# blinkenlights.net
KiCad netlist of a schematic drawn in Altium Designer
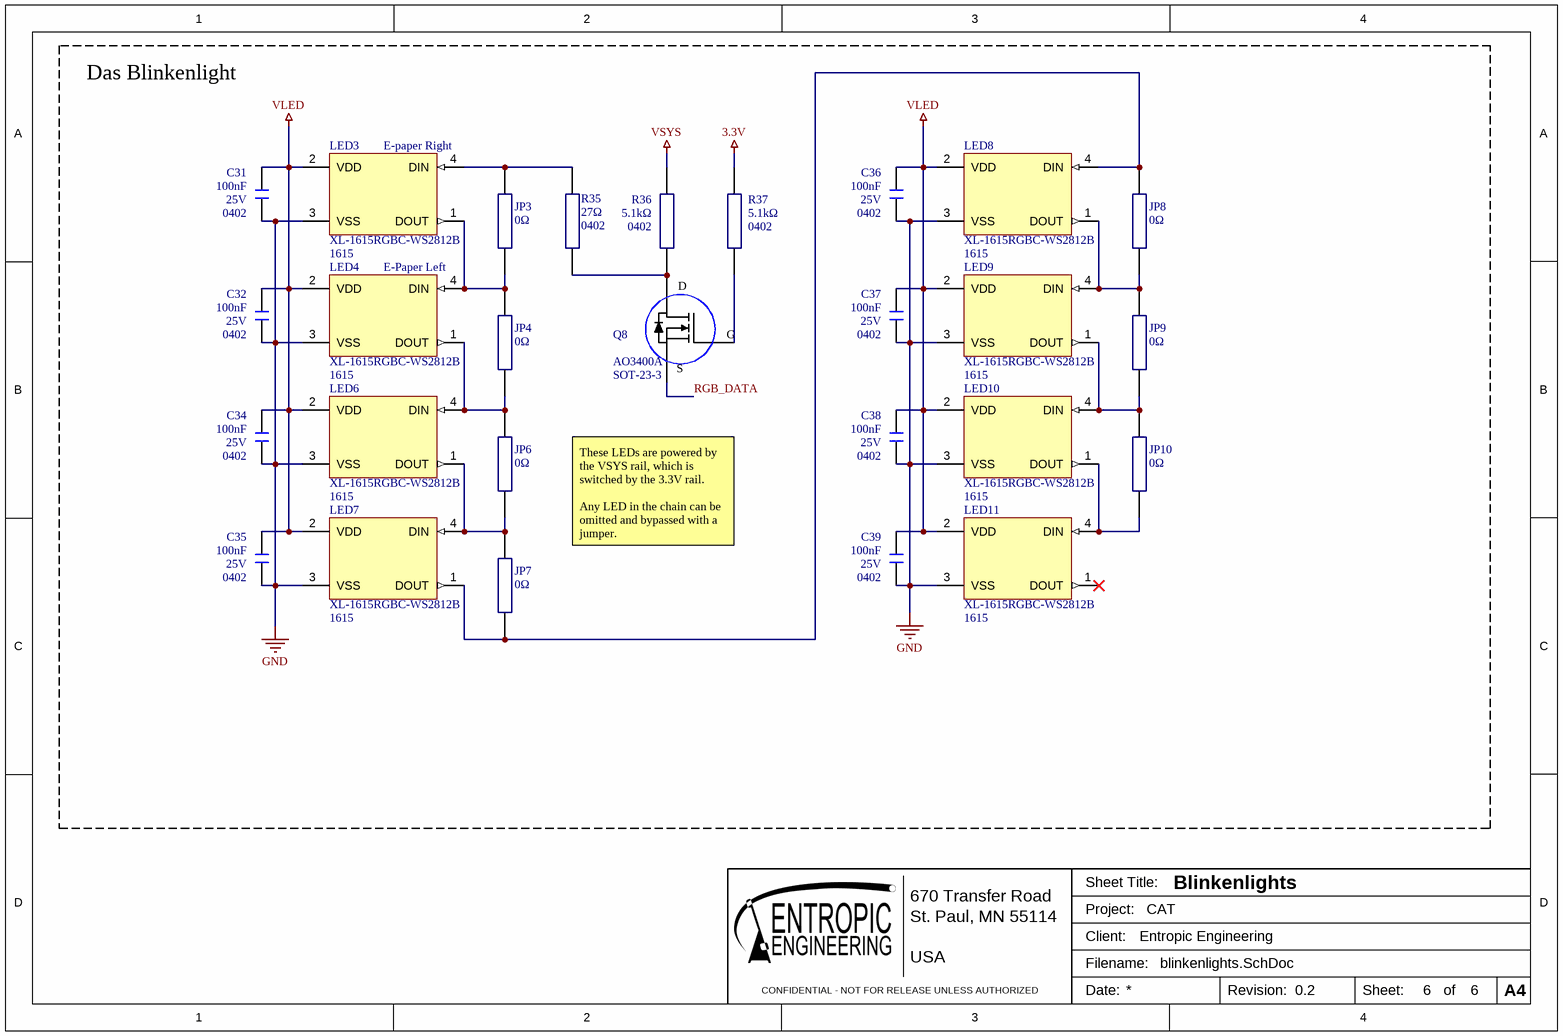
[diagram p0: blinkenlights.SchDoc]

(export (version "E")
  (design (tool "Eeschema 10.0.6"))
  (components
    (comp (ref "C31")
      (value "GRM155R71E104KE14D")
      (footprint "0402_capacitor")
      (description "100 nF, 25 V, X7R, 0402 Chip capacitor")
      (fields
        (field (name "MANUFACTURER") "Murata")
        (field (name "TOLERANCE") "10%")
        (field (name "CASE CODE (IMPERIAL)") "0402")
        (field (name "VOLTAGE") "25V")
        (field (name "CAPACITANCE") "100nF")
      )
      (libsource (lib "cat") (part "GRM155R71E104KE14D"))
    )
    (comp (ref "C32")
      (value "GRM155R71E104KE14D")
      (footprint "0402_capacitor")
      (description "100 nF, 25 V, X7R, 0402 Chip capacitor")
      (fields
        (field (name "MANUFACTURER") "Murata")
        (field (name "TOLERANCE") "10%")
        (field (name "CASE CODE (IMPERIAL)") "0402")
        (field (name "VOLTAGE") "25V")
        (field (name "CAPACITANCE") "100nF")
      )
      (libsource (lib "cat") (part "GRM155R71E104KE14D"))
    )
    (comp (ref "C34")
      (value "GRM155R71E104KE14D")
      (footprint "0402_capacitor")
      (description "100 nF, 25 V, X7R, 0402 Chip capacitor")
      (fields
        (field (name "MANUFACTURER") "Murata")
        (field (name "TOLERANCE") "10%")
        (field (name "CASE CODE (IMPERIAL)") "0402")
        (field (name "VOLTAGE") "25V")
        (field (name "CAPACITANCE") "100nF")
      )
      (libsource (lib "cat") (part "GRM155R71E104KE14D"))
    )
    (comp (ref "C35")
      (value "GRM155R71E104KE14D")
      (footprint "0402_capacitor")
      (description "100 nF, 25 V, X7R, 0402 Chip capacitor")
      (fields
        (field (name "MANUFACTURER") "Murata")
        (field (name "TOLERANCE") "10%")
        (field (name "CASE CODE (IMPERIAL)") "0402")
        (field (name "VOLTAGE") "25V")
        (field (name "CAPACITANCE") "100nF")
      )
      (libsource (lib "cat") (part "GRM155R71E104KE14D"))
    )
    (comp (ref "C36")
      (value "GRM155R71E104KE14D")
      (footprint "0402_capacitor")
      (description "100 nF, 25 V, X7R, 0402 Chip capacitor")
      (fields
        (field (name "MANUFACTURER") "Murata")
        (field (name "TOLERANCE") "10%")
        (field (name "CASE CODE (IMPERIAL)") "0402")
        (field (name "VOLTAGE") "25V")
        (field (name "CAPACITANCE") "100nF")
      )
      (libsource (lib "cat") (part "GRM155R71E104KE14D"))
    )
    (comp (ref "C37")
      (value "GRM155R71E104KE14D")
      (footprint "0402_capacitor")
      (description "100 nF, 25 V, X7R, 0402 Chip capacitor")
      (fields
        (field (name "MANUFACTURER") "Murata")
        (field (name "TOLERANCE") "10%")
        (field (name "CASE CODE (IMPERIAL)") "0402")
        (field (name "VOLTAGE") "25V")
        (field (name "CAPACITANCE") "100nF")
      )
      (libsource (lib "cat") (part "GRM155R71E104KE14D"))
    )
    (comp (ref "C38")
      (value "GRM155R71E104KE14D")
      (footprint "0402_capacitor")
      (description "100 nF, 25 V, X7R, 0402 Chip capacitor")
      (fields
        (field (name "MANUFACTURER") "Murata")
        (field (name "TOLERANCE") "10%")
        (field (name "CASE CODE (IMPERIAL)") "0402")
        (field (name "VOLTAGE") "25V")
        (field (name "CAPACITANCE") "100nF")
      )
      (libsource (lib "cat") (part "GRM155R71E104KE14D"))
    )
    (comp (ref "C39")
      (value "GRM155R71E104KE14D")
      (footprint "0402_capacitor")
      (description "100 nF, 25 V, X7R, 0402 Chip capacitor")
      (fields
        (field (name "MANUFACTURER") "Murata")
        (field (name "TOLERANCE") "10%")
        (field (name "CASE CODE (IMPERIAL)") "0402")
        (field (name "VOLTAGE") "25V")
        (field (name "CAPACITANCE") "100nF")
      )
      (libsource (lib "cat") (part "GRM155R71E104KE14D"))
    )
    (comp (ref "JP3")
      (value "0Ω")
      (footprint "0402_resistor")
      (description "0 Ω, 0402 Chip resistor (jumper)")
      (fields
        (field (name "MANUFACTURER") "Yageo")
        (field (name "MANUFACTURER PART NUMBER") "RC0402FR-070RL")
      )
      (libsource (lib "cat") (part "RC0402FR-070RL"))
    )
    (comp (ref "JP4")
      (value "0Ω")
      (footprint "0402_resistor")
      (description "0 Ω, 0402 Chip resistor (jumper)")
      (fields
        (field (name "MANUFACTURER") "Yageo")
        (field (name "MANUFACTURER PART NUMBER") "RC0402FR-070RL")
      )
      (libsource (lib "cat") (part "RC0402FR-070RL"))
    )
    (comp (ref "JP6")
      (value "0Ω")
      (footprint "0402_resistor")
      (description "0 Ω, 0402 Chip resistor (jumper)")
      (fields
        (field (name "MANUFACTURER") "Yageo")
        (field (name "MANUFACTURER PART NUMBER") "RC0402FR-070RL")
      )
      (libsource (lib "cat") (part "RC0402FR-070RL"))
    )
    (comp (ref "JP7")
      (value "0Ω")
      (footprint "0402_resistor")
      (description "0 Ω, 0402 Chip resistor (jumper)")
      (fields
        (field (name "MANUFACTURER") "Yageo")
        (field (name "MANUFACTURER PART NUMBER") "RC0402FR-070RL")
      )
      (libsource (lib "cat") (part "RC0402FR-070RL"))
    )
    (comp (ref "JP8")
      (value "0Ω")
      (footprint "0402_resistor")
      (description "0 Ω, 0402 Chip resistor (jumper)")
      (fields
        (field (name "MANUFACTURER") "Yageo")
        (field (name "MANUFACTURER PART NUMBER") "RC0402FR-070RL")
      )
      (libsource (lib "cat") (part "RC0402FR-070RL"))
    )
    (comp (ref "JP9")
      (value "0Ω")
      (footprint "0402_resistor")
      (description "0 Ω, 0402 Chip resistor (jumper)")
      (fields
        (field (name "MANUFACTURER") "Yageo")
        (field (name "MANUFACTURER PART NUMBER") "RC0402FR-070RL")
      )
      (libsource (lib "cat") (part "RC0402FR-070RL"))
    )
    (comp (ref "JP10")
      (value "0Ω")
      (footprint "0402_resistor")
      (description "0 Ω, 0402 Chip resistor (jumper)")
      (fields
        (field (name "MANUFACTURER") "Yageo")
        (field (name "MANUFACTURER PART NUMBER") "RC0402FR-070RL")
      )
      (libsource (lib "cat") (part "RC0402FR-070RL"))
    )
    (comp (ref "LED3")
      (value "E-paper Right")
      (footprint "XL-1615RGBC-WS2812B")
      (description "1-wire addressable RGB LED, 1615")
      (fields
        (field (name "MANUFACTURER") "XINGLIGHT")
        (field (name "MANUFACTURER PART NUMBER") "XL-1615RGBC-WS2812B")
        (field (name "PACKAGE") "1615")
      )
      (libsource (lib "cat") (part "XL-1615RGBC-WS2812B"))
    )
    (comp (ref "LED4")
      (value "E-Paper Left")
      (footprint "XL-1615RGBC-WS2812B")
      (description "1-wire addressable RGB LED, 1615")
      (fields
        (field (name "MANUFACTURER") "XINGLIGHT")
        (field (name "MANUFACTURER PART NUMBER") "XL-1615RGBC-WS2812B")
        (field (name "PACKAGE") "1615")
      )
      (libsource (lib "cat") (part "XL-1615RGBC-WS2812B"))
    )
    (comp (ref "LED6")
      (value "XL-1615RGBC-WS2812B")
      (footprint "XL-1615RGBC-WS2812B")
      (description "1-wire addressable RGB LED, 1615")
      (fields
        (field (name "MANUFACTURER") "XINGLIGHT")
        (field (name "MANUFACTURER PART NUMBER") "XL-1615RGBC-WS2812B")
        (field (name "PACKAGE") "1615")
      )
      (libsource (lib "cat") (part "XL-1615RGBC-WS2812B"))
    )
    (comp (ref "LED7")
      (value "WS2812B")
      (footprint "XL-1615RGBC-WS2812B")
      (description "1-wire addressable RGB LED, 1615")
      (fields
        (field (name "MANUFACTURER") "XINGLIGHT")
        (field (name "MANUFACTURER PART NUMBER") "XL-1615RGBC-WS2812B")
        (field (name "PACKAGE") "1615")
      )
      (libsource (lib "cat") (part "XL-1615RGBC-WS2812B"))
    )
    (comp (ref "LED8")
      (value "XL-1615RGBC-WS2812B")
      (footprint "XL-1615RGBC-WS2812B")
      (description "1-wire addressable RGB LED, 1615")
      (fields
        (field (name "MANUFACTURER") "XINGLIGHT")
        (field (name "MANUFACTURER PART NUMBER") "XL-1615RGBC-WS2812B")
        (field (name "PACKAGE") "1615")
      )
      (libsource (lib "cat") (part "XL-1615RGBC-WS2812B"))
    )
    (comp (ref "LED9")
      (value "WS2812B")
      (footprint "XL-1615RGBC-WS2812B")
      (description "1-wire addressable RGB LED, 1615")
      (fields
        (field (name "MANUFACTURER") "XINGLIGHT")
        (field (name "MANUFACTURER PART NUMBER") "XL-1615RGBC-WS2812B")
        (field (name "PACKAGE") "1615")
      )
      (libsource (lib "cat") (part "XL-1615RGBC-WS2812B"))
    )
    (comp (ref "LED10")
      (value "XL-1615RGBC-WS2812B")
      (footprint "XL-1615RGBC-WS2812B")
      (description "1-wire addressable RGB LED, 1615")
      (fields
        (field (name "MANUFACTURER") "XINGLIGHT")
        (field (name "MANUFACTURER PART NUMBER") "XL-1615RGBC-WS2812B")
        (field (name "PACKAGE") "1615")
      )
      (libsource (lib "cat") (part "XL-1615RGBC-WS2812B"))
    )
    (comp (ref "LED11")
      (value "WS2812B")
      (footprint "XL-1615RGBC-WS2812B")
      (description "1-wire addressable RGB LED, 1615")
      (fields
        (field (name "MANUFACTURER") "XINGLIGHT")
        (field (name "MANUFACTURER PART NUMBER") "XL-1615RGBC-WS2812B")
        (field (name "PACKAGE") "1615")
      )
      (libsource (lib "cat") (part "XL-1615RGBC-WS2812B"))
    )
    (comp (ref "Q8")
      (value "N-FET")
      (footprint "SOT95P280X115-3N")
      (description "N-FET, 30V, 5.7A, SOT-23-3")
      (fields
        (field (name "MANUFACTURER") "Alpha & Omega Semiconductor")
        (field (name "CASE/PACKAGE") "SOT-23-3")
        (field (name "MANUFACTURER PART NUMBER") "AO3400A")
        (field (name "HOUSE_PART_NUMBER") "AO3400A")
      )
      (libsource (lib "cat") (part "AO3400A"))
    )
    (comp (ref "R35")
      (value "RMCF0402FT27R0")
      (footprint "0402_resistor")
      (description "27 Ω, 0402 Chip resistor")
      (fields
        (field (name "MANUFACTURER") "Stackpole Electronics")
        (field (name "TOLERANCE") "1%")
        (field (name "RESISTANCE") "27Ω")
        (field (name "SIZE CODE") "0402")
      )
      (libsource (lib "cat") (part "RMCF0402FT27R0"))
    )
    (comp (ref "R36")
      (value "5.1kΩ")
      (footprint "0402_resistor")
      (description "5.1 kΩ, 0402 Chip resistor")
      (fields
        (field (name "MANUFACTURER") "Yageo")
        (field (name "MANUFACTURER PART NUMBER") "RC0402FR-075K1L")
        (field (name "CASE/PACKAGE") "0402")
      )
      (libsource (lib "cat") (part "RC0402FR-075K1L"))
    )
    (comp (ref "R37")
      (value "5.1kΩ")
      (footprint "0402_resistor")
      (description "5.1 kΩ, 0402 Chip resistor")
      (fields
        (field (name "MANUFACTURER") "Yageo")
        (field (name "MANUFACTURER PART NUMBER") "RC0402FR-075K1L")
        (field (name "CASE/PACKAGE") "0402")
      )
      (libsource (lib "cat") (part "RC0402FR-075K1L"))
    )
  )
  (nets
    (net (code "1") (name "/RGB_DATA") (class "Default")
      (node (ref "Q8") (pin "2") (pinfunction "S_2") (pintype "passive"))
    )
    (net (code "2") (name "3.3V") (class "Default")
      (node (ref "R37") (pin "2") (pinfunction "2_2") (pintype "passive"))
    )
    (net (code "3") (name "GND") (class "Default")
      (node (ref "C31") (pin "1") (pinfunction "1_1") (pintype "passive"))
      (node (ref "C32") (pin "1") (pinfunction "1_1") (pintype "passive"))
      (node (ref "C34") (pin "1") (pinfunction "1_1") (pintype "passive"))
      (node (ref "C35") (pin "1") (pinfunction "1_1") (pintype "passive"))
      (node (ref "C36") (pin "1") (pinfunction "1_1") (pintype "passive"))
      (node (ref "C37") (pin "1") (pinfunction "1_1") (pintype "passive"))
      (node (ref "C38") (pin "1") (pinfunction "1_1") (pintype "passive"))
      (node (ref "C39") (pin "1") (pinfunction "1_1") (pintype "passive"))
      (node (ref "LED10") (pin "3") (pinfunction "VSS_3") (pintype "power_in"))
      (node (ref "LED11") (pin "3") (pinfunction "VSS_3") (pintype "power_in"))
      (node (ref "LED3") (pin "3") (pinfunction "VSS_3") (pintype "power_in"))
      (node (ref "LED4") (pin "3") (pinfunction "VSS_3") (pintype "power_in"))
      (node (ref "LED6") (pin "3") (pinfunction "VSS_3") (pintype "power_in"))
      (node (ref "LED7") (pin "3") (pinfunction "VSS_3") (pintype "power_in"))
      (node (ref "LED8") (pin "3") (pinfunction "VSS_3") (pintype "power_in"))
      (node (ref "LED9") (pin "3") (pinfunction "VSS_3") (pintype "power_in"))
    )
    (net (code "4") (name "Net-(LED3-DIN)") (class "Default")
      (node (ref "JP3") (pin "1") (pinfunction "1_1") (pintype "passive"))
      (node (ref "LED3") (pin "4") (pinfunction "DIN_4") (pintype "input"))
      (node (ref "R35") (pin "2") (pinfunction "2_2") (pintype "passive"))
    )
    (net (code "5") (name "Net-(LED3-DOUT)") (class "Default")
      (node (ref "JP3") (pin "2") (pinfunction "2_2") (pintype "passive"))
      (node (ref "JP4") (pin "1") (pinfunction "1_1") (pintype "passive"))
      (node (ref "LED3") (pin "1") (pinfunction "DOUT_1") (pintype "output"))
      (node (ref "LED4") (pin "4") (pinfunction "DIN_4") (pintype "input"))
    )
    (net (code "6") (name "Net-(LED4-DOUT)") (class "Default")
      (node (ref "JP4") (pin "2") (pinfunction "2_2") (pintype "passive"))
      (node (ref "JP6") (pin "1") (pinfunction "1_1") (pintype "passive"))
      (node (ref "LED4") (pin "1") (pinfunction "DOUT_1") (pintype "output"))
      (node (ref "LED6") (pin "4") (pinfunction "DIN_4") (pintype "input"))
    )
    (net (code "7") (name "Net-(LED6-DOUT)") (class "Default")
      (node (ref "JP6") (pin "2") (pinfunction "2_2") (pintype "passive"))
      (node (ref "JP7") (pin "1") (pinfunction "1_1") (pintype "passive"))
      (node (ref "LED6") (pin "1") (pinfunction "DOUT_1") (pintype "output"))
      (node (ref "LED7") (pin "4") (pinfunction "DIN_4") (pintype "input"))
    )
    (net (code "8") (name "Net-(LED7-DOUT)") (class "Default")
      (node (ref "JP7") (pin "2") (pinfunction "2_2") (pintype "passive"))
      (node (ref "JP8") (pin "1") (pinfunction "1_1") (pintype "passive"))
      (node (ref "LED7") (pin "1") (pinfunction "DOUT_1") (pintype "output"))
      (node (ref "LED8") (pin "4") (pinfunction "DIN_4") (pintype "input"))
    )
    (net (code "9") (name "Net-(LED8-DOUT)") (class "Default")
      (node (ref "JP8") (pin "2") (pinfunction "2_2") (pintype "passive"))
      (node (ref "JP9") (pin "1") (pinfunction "1_1") (pintype "passive"))
      (node (ref "LED8") (pin "1") (pinfunction "DOUT_1") (pintype "output"))
      (node (ref "LED9") (pin "4") (pinfunction "DIN_4") (pintype "input"))
    )
    (net (code "10") (name "Net-(LED10-DIN)") (class "Default")
      (node (ref "JP10") (pin "1") (pinfunction "1_1") (pintype "passive"))
      (node (ref "JP9") (pin "2") (pinfunction "2_2") (pintype "passive"))
      (node (ref "LED10") (pin "4") (pinfunction "DIN_4") (pintype "input"))
      (node (ref "LED9") (pin "1") (pinfunction "DOUT_1") (pintype "output"))
    )
    (net (code "11") (name "Net-(LED10-DOUT)") (class "Default")
      (node (ref "JP10") (pin "2") (pinfunction "2_2") (pintype "passive"))
      (node (ref "LED10") (pin "1") (pinfunction "DOUT_1") (pintype "output"))
      (node (ref "LED11") (pin "4") (pinfunction "DIN_4") (pintype "input"))
    )
    (net (code "12") (name "Net-(Q8-D)") (class "Default")
      (node (ref "Q8") (pin "3") (pinfunction "D_3") (pintype "passive"))
      (node (ref "R35") (pin "1") (pinfunction "1_1") (pintype "passive"))
      (node (ref "R36") (pin "1") (pinfunction "1_1") (pintype "passive"))
    )
    (net (code "13") (name "Net-(Q8-G)") (class "Default")
      (node (ref "Q8") (pin "1") (pinfunction "G_1") (pintype "passive"))
      (node (ref "R37") (pin "1") (pinfunction "1_1") (pintype "passive"))
    )
    (net (code "14") (name "VLED") (class "Default")
      (node (ref "C31") (pin "2") (pinfunction "2_2") (pintype "passive"))
      (node (ref "C32") (pin "2") (pinfunction "2_2") (pintype "passive"))
      (node (ref "C34") (pin "2") (pinfunction "2_2") (pintype "passive"))
      (node (ref "C35") (pin "2") (pinfunction "2_2") (pintype "passive"))
      (node (ref "C36") (pin "2") (pinfunction "2_2") (pintype "passive"))
      (node (ref "C37") (pin "2") (pinfunction "2_2") (pintype "passive"))
      (node (ref "C38") (pin "2") (pinfunction "2_2") (pintype "passive"))
      (node (ref "C39") (pin "2") (pinfunction "2_2") (pintype "passive"))
      (node (ref "LED10") (pin "2") (pinfunction "VDD_2") (pintype "power_in"))
      (node (ref "LED11") (pin "2") (pinfunction "VDD_2") (pintype "power_in"))
      (node (ref "LED3") (pin "2") (pinfunction "VDD_2") (pintype "power_in"))
      (node (ref "LED4") (pin "2") (pinfunction "VDD_2") (pintype "power_in"))
      (node (ref "LED6") (pin "2") (pinfunction "VDD_2") (pintype "power_in"))
      (node (ref "LED7") (pin "2") (pinfunction "VDD_2") (pintype "power_in"))
      (node (ref "LED8") (pin "2") (pinfunction "VDD_2") (pintype "power_in"))
      (node (ref "LED9") (pin "2") (pinfunction "VDD_2") (pintype "power_in"))
    )
    (net (code "15") (name "VSYS") (class "Default")
      (node (ref "R36") (pin "2") (pinfunction "2_2") (pintype "passive"))
    )
    (net (code "16") (name "unconnected-(LED11-DOUT-Pad1)") (class "Default")
      (node (ref "LED11") (pin "1") (pinfunction "DOUT_1") (pintype "output+no_connect"))
    )
  )
)
